# sb5.net
KiCad netlist of a schematic drawn in EAGLE
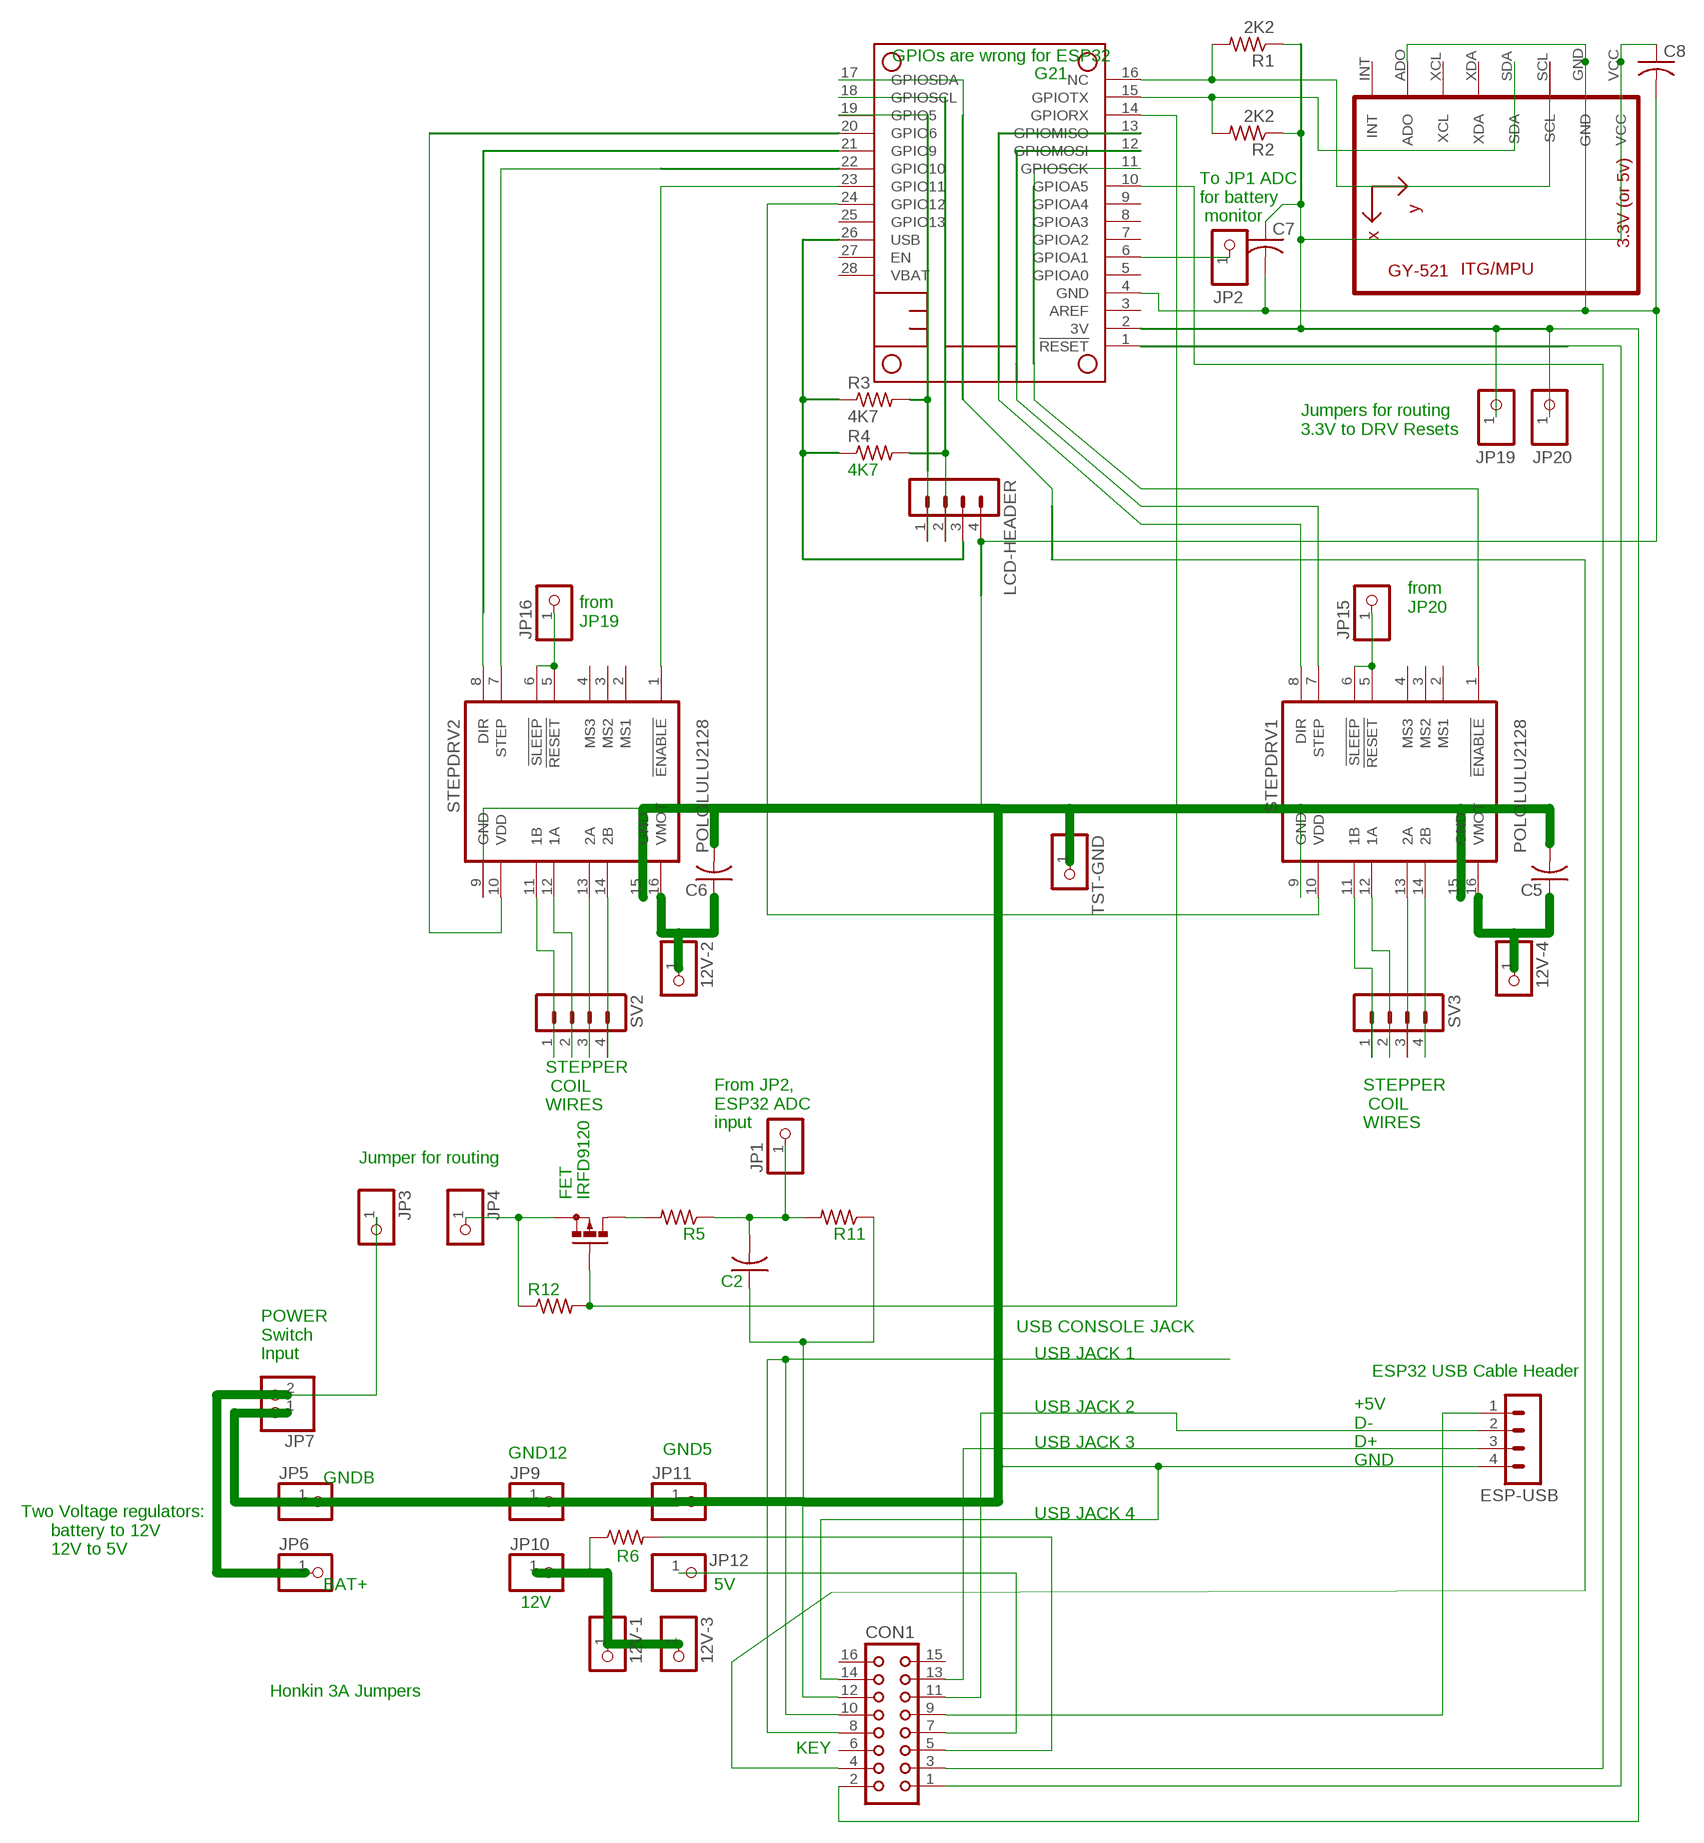
[diagram p0: schematic, sheet 1]

(export (version "E")
  (design (tool "Eeschema 10.0.6"))
  (components
    (comp (ref "12V-1")
      (value "PINHD-1X1")
      (footprint "eagle-import:1X01")
      (libsource (lib "eagle-import") (part "PINHD-1X1"))
    )
    (comp (ref "12V-2")
      (value "PINHD-1X1")
      (footprint "eagle-import:1X01")
      (libsource (lib "eagle-import") (part "PINHD-1X1"))
    )
    (comp (ref "12V-3")
      (value "PINHD-1X1")
      (footprint "eagle-import:1X01")
      (libsource (lib "eagle-import") (part "PINHD-1X1"))
    )
    (comp (ref "12V-4")
      (value "PINHD-1X1")
      (footprint "eagle-import:1X01")
      (libsource (lib "eagle-import") (part "PINHD-1X1"))
    )
    (comp (ref "C2")
      (value "C-US050-025X075")
      (footprint "eagle-import:C050-025X075")
      (libsource (lib "eagle-import") (part "C-US050-025X075"))
    )
    (comp (ref "C5")
      (value "C-US050-024X044")
      (footprint "eagle-import:C050-024X044")
      (libsource (lib "eagle-import") (part "C-US050-024X044"))
    )
    (comp (ref "C6")
      (value "C-US050-024X044")
      (footprint "eagle-import:C050-024X044")
      (libsource (lib "eagle-import") (part "C-US050-024X044"))
    )
    (comp (ref "C7")
      (value "C-US050-024X044")
      (footprint "eagle-import:C050-024X044")
      (libsource (lib "eagle-import") (part "C-US050-024X044"))
    )
    (comp (ref "C8")
      (value "C-US050-024X044")
      (footprint "eagle-import:C050-024X044")
      (libsource (lib "eagle-import") (part "C-US050-024X044"))
    )
    (comp (ref "CON1")
      (value "CON16")
      (footprint "eagle-import:CON16")
      (libsource (lib "eagle-import") (part "CON16"))
    )
    (comp (ref "ESP-USB")
      (value "MA04-1")
      (footprint "eagle-import:MA04-1")
      (libsource (lib "eagle-import") (part "MA04-1"))
    )
    (comp (ref "FET")
      (value "IRFD9120")
      (footprint "eagle-import:C370-01")
      (libsource (lib "eagle-import") (part "IRFD9120"))
    )
    (comp (ref "JP1")
      (value "PINHD-1X1")
      (footprint "eagle-import:1X01")
      (libsource (lib "eagle-import") (part "PINHD-1X1"))
    )
    (comp (ref "JP2")
      (value "PINHD-1X1")
      (footprint "eagle-import:1X01")
      (libsource (lib "eagle-import") (part "PINHD-1X1"))
    )
    (comp (ref "JP3")
      (value "PINHD-1X1")
      (footprint "eagle-import:1X01")
      (libsource (lib "eagle-import") (part "PINHD-1X1"))
    )
    (comp (ref "JP4")
      (value "PINHD-1X1")
      (footprint "eagle-import:1X01")
      (libsource (lib "eagle-import") (part "PINHD-1X1"))
    )
    (comp (ref "JP5")
      (value "PINHD-1X1")
      (footprint "eagle-import:1X01")
      (libsource (lib "eagle-import") (part "PINHD-1X1"))
    )
    (comp (ref "JP6")
      (value "PINHD-1X1")
      (footprint "eagle-import:1X01")
      (libsource (lib "eagle-import") (part "PINHD-1X1"))
    )
    (comp (ref "JP7")
      (value "PINHD-1X2")
      (footprint "eagle-import:1X02")
      (libsource (lib "eagle-import") (part "PINHD-1X2"))
    )
    (comp (ref "JP9")
      (value "PINHD-1X1")
      (footprint "eagle-import:1X01")
      (libsource (lib "eagle-import") (part "PINHD-1X1"))
    )
    (comp (ref "JP10")
      (value "PINHD-1X1")
      (footprint "eagle-import:1X01")
      (libsource (lib "eagle-import") (part "PINHD-1X1"))
    )
    (comp (ref "JP11")
      (value "PINHD-1X1")
      (footprint "eagle-import:1X01")
      (libsource (lib "eagle-import") (part "PINHD-1X1"))
    )
    (comp (ref "JP12")
      (value "PINHD-1X1")
      (footprint "eagle-import:1X01")
      (libsource (lib "eagle-import") (part "PINHD-1X1"))
    )
    (comp (ref "JP15")
      (value "PINHD-1X1")
      (footprint "eagle-import:1X01")
      (libsource (lib "eagle-import") (part "PINHD-1X1"))
    )
    (comp (ref "JP16")
      (value "PINHD-1X1")
      (footprint "eagle-import:1X01")
      (libsource (lib "eagle-import") (part "PINHD-1X1"))
    )
    (comp (ref "JP19")
      (value "PINHD-1X1")
      (footprint "eagle-import:1X01")
      (libsource (lib "eagle-import") (part "PINHD-1X1"))
    )
    (comp (ref "JP20")
      (value "PINHD-1X1")
      (footprint "eagle-import:1X01")
      (libsource (lib "eagle-import") (part "PINHD-1X1"))
    )
    (comp (ref "LCD-HEADER")
      (value "MA04-1")
      (footprint "eagle-import:MA04-1")
      (libsource (lib "eagle-import") (part "MA04-1"))
    )
    (comp (ref "MS2")
      (value "FEATHERWING_NOHOLES")
      (footprint "eagle-import:FEATHERWING_NOHOLES")
      (libsource (lib "eagle-import") (part "FEATHERWING_NOHOLES"))
    )
    (comp (ref "R1")
      (value "2K2")
      (footprint "eagle-import:0309_12")
      (libsource (lib "eagle-import") (part "resistor_348_R-US_0309/12"))
    )
    (comp (ref "R2")
      (value "2K2")
      (footprint "eagle-import:0309_12")
      (libsource (lib "eagle-import") (part "resistor_348_R-US_0309/12"))
    )
    (comp (ref "R3")
      (value "4K7")
      (footprint "eagle-import:0309_12")
      (libsource (lib "eagle-import") (part "resistor_348_R-US_0309/12"))
    )
    (comp (ref "R4")
      (value "4K7")
      (footprint "eagle-import:0309_12")
      (libsource (lib "eagle-import") (part "resistor_348_R-US_0309/12"))
    )
    (comp (ref "R5")
      (value "R-US_0207/10")
      (footprint "eagle-import:0207_10")
      (libsource (lib "eagle-import") (part "R-US_0207/10"))
    )
    (comp (ref "R6")
      (value "R-US_0207/10")
      (footprint "eagle-import:0207_10")
      (libsource (lib "eagle-import") (part "R-US_0207/10"))
    )
    (comp (ref "R11")
      (value "R-US_0207/10")
      (footprint "eagle-import:0207_10")
      (libsource (lib "eagle-import") (part "R-US_0207/10"))
    )
    (comp (ref "R12")
      (value "R-US_0207/10")
      (footprint "eagle-import:0207_10")
      (libsource (lib "eagle-import") (part "R-US_0207/10"))
    )
    (comp (ref "STEPDRV1")
      (value "POLOLULU2128")
      (footprint "eagle-import:POLOLULU2128")
      (libsource (lib "eagle-import") (part "POLOLULU2128"))
    )
    (comp (ref "STEPDRV2")
      (value "POLOLULU2128")
      (footprint "eagle-import:POLOLULU2128")
      (libsource (lib "eagle-import") (part "POLOLULU2128"))
    )
    (comp (ref "SV2")
      (value "MA04-1")
      (footprint "eagle-import:MA04-1")
      (libsource (lib "eagle-import") (part "MA04-1"))
    )
    (comp (ref "SV3")
      (value "MA04-1")
      (footprint "eagle-import:MA04-1")
      (libsource (lib "eagle-import") (part "MA04-1"))
    )
    (comp (ref "TST-GND")
      (value "PINHD-1X1")
      (footprint "eagle-import:1X01")
      (libsource (lib "eagle-import") (part "PINHD-1X1"))
    )
    (comp (ref "U1")
      (value "GY-521MPU6050")
      (footprint "eagle-import:GY-521")
      (libsource (lib "eagle-import") (part "GY-521MPU6050"))
    )
  )
  (nets
    (net (code "1") (name "/VBAT") (class "Default")
      (node (ref "MS2") (pin "28") (pinfunction "VBAT_28") (pintype "power_in"))
    )
    (net (code "2") (name "Net-(12V-1-Pad1)") (class "Default")
      (node (ref "12V-1") (pin "1") (pinfunction "1_1") (pintype "passive"))
      (node (ref "12V-3") (pin "1") (pinfunction "1_1") (pintype "passive"))
      (node (ref "JP10") (pin "1") (pinfunction "1_1") (pintype "passive"))
      (node (ref "R6") (pin "1") (pinfunction "1_1") (pintype "passive"))
    )
    (net (code "3") (name "Net-(C2-Pad2)") (class "Default")
      (node (ref "C2") (pin "2") (pinfunction "2_2") (pintype "passive"))
      (node (ref "JP1") (pin "1") (pinfunction "1_1") (pintype "passive"))
      (node (ref "R11") (pin "2") (pinfunction "2_2") (pintype "passive"))
      (node (ref "R5") (pin "1") (pinfunction "1_1") (pintype "passive"))
    )
    (net (code "4") (name "Net-(CON1-Pad5)") (class "Default")
      (node (ref "CON1") (pin "5") (pinfunction "5_5") (pintype "passive"))
      (node (ref "R6") (pin "2") (pinfunction "2_2") (pintype "passive"))
    )
    (net (code "5") (name "Net-(CON1-Pad7)") (class "Default")
      (node (ref "CON1") (pin "7") (pinfunction "7_7") (pintype "passive"))
      (node (ref "JP12") (pin "1") (pinfunction "1_1") (pintype "passive"))
    )
    (net (code "6") (name "Net-(CON1-Pad9)") (class "Default")
      (node (ref "CON1") (pin "9") (pinfunction "9_9") (pintype "passive"))
      (node (ref "ESP-USB") (pin "1") (pinfunction "1_1") (pintype "passive"))
    )
    (net (code "7") (name "Net-(CON1-Pad10)") (class "Default")
      (node (ref "CON1") (pin "10") (pinfunction "10_10") (pintype "passive"))
      (node (ref "CON1") (pin "8") (pinfunction "8_8") (pintype "passive"))
    )
    (net (code "8") (name "Net-(CON1-Pad11)") (class "Default")
      (node (ref "CON1") (pin "11") (pinfunction "11_11") (pintype "passive"))
      (node (ref "ESP-USB") (pin "2") (pinfunction "2_2") (pintype "passive"))
    )
    (net (code "9") (name "Net-(CON1-Pad13)") (class "Default")
      (node (ref "CON1") (pin "13") (pinfunction "13_13") (pintype "passive"))
      (node (ref "ESP-USB") (pin "3") (pinfunction "3_3") (pintype "passive"))
    )
    (net (code "10") (name "Net-(FET-D-PadD1)") (class "Default")
      (node (ref "FET") (pin "D") (pinfunction "D_D") (pintype "passive"))
      (node (ref "FET") (pin "D1") (pinfunction "D_D1") (pintype "passive"))
      (node (ref "R5") (pin "2") (pinfunction "2_2") (pintype "passive"))
    )
    (net (code "11") (name "Net-(FET-PadS)") (class "Default")
      (node (ref "FET") (pin "S") (pinfunction "S_S") (pintype "passive"))
      (node (ref "JP4") (pin "1") (pinfunction "1_1") (pintype "passive"))
      (node (ref "R12") (pin "1") (pinfunction "1_1") (pintype "passive"))
    )
    (net (code "12") (name "Net-(JP3-Pad1)") (class "Default")
      (node (ref "JP3") (pin "1") (pinfunction "1_1") (pintype "passive"))
      (node (ref "JP6") (pin "1") (pinfunction "1_1") (pintype "passive"))
      (node (ref "JP7") (pin "2") (pinfunction "2_2") (pintype "passive"))
    )
    (net (code "13") (name "Net-(MS2-3V)") (class "Default")
      (node (ref "C7") (pin "1") (pinfunction "1_1") (pintype "passive"))
      (node (ref "C8") (pin "1") (pinfunction "1_1") (pintype "passive"))
      (node (ref "CON1") (pin "2") (pinfunction "2_2") (pintype "passive"))
      (node (ref "JP19") (pin "1") (pinfunction "1_1") (pintype "passive"))
      (node (ref "JP20") (pin "1") (pinfunction "1_1") (pintype "passive"))
      (node (ref "MS2") (pin "2") (pinfunction "3V_2") (pintype "power_in"))
      (node (ref "R1") (pin "1") (pinfunction "1_1") (pintype "passive"))
      (node (ref "R2") (pin "1") (pinfunction "1_1") (pintype "passive"))
      (node (ref "U1") (pin "VCC") (pinfunction "VCC_VCC") (pintype "bidirectional"))
    )
    (net (code "14") (name "Net-(MS2-GND)") (class "Default")
      (node (ref "C2") (pin "1") (pinfunction "1_1") (pintype "passive"))
      (node (ref "C5") (pin "2") (pinfunction "2_2") (pintype "passive"))
      (node (ref "C6") (pin "2") (pinfunction "2_2") (pintype "passive"))
      (node (ref "C7") (pin "2") (pinfunction "2_2") (pintype "passive"))
      (node (ref "C8") (pin "2") (pinfunction "2_2") (pintype "passive"))
      (node (ref "CON1") (pin "12") (pinfunction "12_12") (pintype "passive"))
      (node (ref "CON1") (pin "14") (pinfunction "14_14") (pintype "passive"))
      (node (ref "ESP-USB") (pin "4") (pinfunction "4_4") (pintype "passive"))
      (node (ref "JP11") (pin "1") (pinfunction "1_1") (pintype "passive"))
      (node (ref "JP5") (pin "1") (pinfunction "1_1") (pintype "passive"))
      (node (ref "JP7") (pin "1") (pinfunction "1_1") (pintype "passive"))
      (node (ref "JP9") (pin "1") (pinfunction "1_1") (pintype "passive"))
      (node (ref "LCD-HEADER") (pin "4") (pinfunction "4_4") (pintype "passive"))
      (node (ref "MS2") (pin "4") (pinfunction "GND_4") (pintype "power_in"))
      (node (ref "R11") (pin "1") (pinfunction "1_1") (pintype "passive"))
      (node (ref "STEPDRV1") (pin "15") (pinfunction "GND_15") (pintype "power_in"))
      (node (ref "STEPDRV1") (pin "9") (pinfunction "GND_9") (pintype "power_in"))
      (node (ref "STEPDRV2") (pin "15") (pinfunction "GND_15") (pintype "power_in"))
      (node (ref "STEPDRV2") (pin "9") (pinfunction "GND_9") (pintype "power_in"))
      (node (ref "TST-GND") (pin "1") (pinfunction "1_1") (pintype "passive"))
      (node (ref "U1") (pin "ADO") (pinfunction "ADO_ADO") (pintype "bidirectional"))
      (node (ref "U1") (pin "GND") (pinfunction "GND_GND") (pintype "bidirectional"))
    )
    (net (code "15") (name "Net-(MS2-GPIO5)") (class "Default")
      (node (ref "LCD-HEADER") (pin "1") (pinfunction "1_1") (pintype "passive"))
      (node (ref "MS2") (pin "19") (pinfunction "GPIO5_19") (pintype "bidirectional"))
      (node (ref "R3") (pin "2") (pinfunction "2_2") (pintype "passive"))
    )
    (net (code "16") (name "Net-(MS2-GPIO6)") (class "Default")
      (node (ref "MS2") (pin "20") (pinfunction "GPIO6_20") (pintype "bidirectional"))
      (node (ref "STEPDRV2") (pin "10") (pinfunction "VDD_10") (pintype "power_in"))
    )
    (net (code "17") (name "Net-(MS2-GPIO9)") (class "Default")
      (node (ref "MS2") (pin "21") (pinfunction "GPIO9_21") (pintype "bidirectional"))
      (node (ref "STEPDRV2") (pin "8") (pinfunction "DIR_8") (pintype "input"))
    )
    (net (code "18") (name "Net-(MS2-GPIO10)") (class "Default")
      (node (ref "MS2") (pin "22") (pinfunction "GPIO10_22") (pintype "bidirectional"))
      (node (ref "STEPDRV2") (pin "7") (pinfunction "STEP_7") (pintype "input"))
    )
    (net (code "19") (name "Net-(MS2-GPIO11)") (class "Default")
      (node (ref "MS2") (pin "23") (pinfunction "GPIO11_23") (pintype "bidirectional"))
      (node (ref "STEPDRV2") (pin "1") (pinfunction "~{ENABLE}_1") (pintype "input"))
    )
    (net (code "20") (name "Net-(MS2-GPIO12)") (class "Default")
      (node (ref "MS2") (pin "24") (pinfunction "GPIO12_24") (pintype "bidirectional"))
      (node (ref "STEPDRV1") (pin "10") (pinfunction "VDD_10") (pintype "power_in"))
    )
    (net (code "21") (name "Net-(MS2-GPIOA1)") (class "Default")
      (node (ref "JP2") (pin "1") (pinfunction "1_1") (pintype "passive"))
      (node (ref "MS2") (pin "6") (pinfunction "GPIOA1_6") (pintype "bidirectional"))
    )
    (net (code "22") (name "Net-(MS2-GPIOA5)") (class "Default")
      (node (ref "CON1") (pin "3") (pinfunction "3_3") (pintype "passive"))
      (node (ref "MS2") (pin "10") (pinfunction "GPIOA5_10") (pintype "bidirectional"))
    )
    (net (code "23") (name "Net-(MS2-GPIOMISO)") (class "Default")
      (node (ref "MS2") (pin "13") (pinfunction "GPIOMISO_13") (pintype "bidirectional"))
      (node (ref "STEPDRV1") (pin "8") (pinfunction "DIR_8") (pintype "input"))
    )
    (net (code "24") (name "Net-(MS2-GPIOMOSI)") (class "Default")
      (node (ref "MS2") (pin "12") (pinfunction "GPIOMOSI_12") (pintype "bidirectional"))
      (node (ref "STEPDRV1") (pin "7") (pinfunction "STEP_7") (pintype "input"))
    )
    (net (code "25") (name "Net-(MS2-GPIORX)") (class "Default")
      (node (ref "FET") (pin "G") (pinfunction "G_G") (pintype "passive"))
      (node (ref "MS2") (pin "14") (pinfunction "GPIORX_14") (pintype "bidirectional"))
      (node (ref "R12") (pin "2") (pinfunction "2_2") (pintype "passive"))
    )
    (net (code "26") (name "Net-(MS2-GPIOSCK)") (class "Default")
      (node (ref "MS2") (pin "11") (pinfunction "GPIOSCK_11") (pintype "bidirectional"))
      (node (ref "STEPDRV1") (pin "1") (pinfunction "~{ENABLE}_1") (pintype "input"))
    )
    (net (code "27") (name "Net-(MS2-GPIOSCL)") (class "Default")
      (node (ref "LCD-HEADER") (pin "2") (pinfunction "2_2") (pintype "passive"))
      (node (ref "MS2") (pin "18") (pinfunction "GPIOSCL_18") (pintype "bidirectional"))
      (node (ref "R4") (pin "2") (pinfunction "2_2") (pintype "passive"))
    )
    (net (code "28") (name "Net-(MS2-GPIOSDA)") (class "Default")
      (node (ref "CON1") (pin "4") (pinfunction "4_4") (pintype "passive"))
      (node (ref "MS2") (pin "17") (pinfunction "GPIOSDA_17") (pintype "bidirectional"))
    )
    (net (code "29") (name "Net-(MS2-GPIOTX)") (class "Default")
      (node (ref "MS2") (pin "15") (pinfunction "GPIOTX_15") (pintype "bidirectional"))
      (node (ref "R2") (pin "2") (pinfunction "2_2") (pintype "passive"))
      (node (ref "U1") (pin "SDA") (pinfunction "SDA_SDA") (pintype "bidirectional"))
    )
    (net (code "30") (name "Net-(MS2-NC)") (class "Default")
      (node (ref "MS2") (pin "16") (pinfunction "NC_16") (pintype "passive"))
      (node (ref "R1") (pin "2") (pinfunction "2_2") (pintype "passive"))
      (node (ref "U1") (pin "SCL") (pinfunction "SCL_SCL") (pintype "bidirectional"))
    )
    (net (code "31") (name "Net-(MS2-USB)") (class "Default")
      (node (ref "LCD-HEADER") (pin "3") (pinfunction "3_3") (pintype "passive"))
      (node (ref "MS2") (pin "26") (pinfunction "USB_26") (pintype "power_in"))
      (node (ref "R3") (pin "1") (pinfunction "1_1") (pintype "passive"))
      (node (ref "R4") (pin "1") (pinfunction "1_1") (pintype "passive"))
    )
    (net (code "32") (name "Net-(MS2-~{RESET})") (class "Default")
      (node (ref "CON1") (pin "1") (pinfunction "1_1") (pintype "passive"))
      (node (ref "MS2") (pin "1") (pinfunction "~{RESET}_1") (pintype "input"))
    )
    (net (code "33") (name "Net-(STEPDRV1-1A)") (class "Default")
      (node (ref "STEPDRV1") (pin "12") (pinfunction "1A_12") (pintype "output"))
      (node (ref "SV3") (pin "2") (pinfunction "2_2") (pintype "passive"))
    )
    (net (code "34") (name "Net-(STEPDRV1-1B)") (class "Default")
      (node (ref "STEPDRV1") (pin "11") (pinfunction "1B_11") (pintype "output"))
      (node (ref "SV3") (pin "1") (pinfunction "1_1") (pintype "passive"))
    )
    (net (code "35") (name "Net-(STEPDRV1-2A)") (class "Default")
      (node (ref "STEPDRV1") (pin "13") (pinfunction "2A_13") (pintype "output"))
      (node (ref "SV3") (pin "3") (pinfunction "3_3") (pintype "passive"))
    )
    (net (code "36") (name "Net-(STEPDRV1-2B)") (class "Default")
      (node (ref "STEPDRV1") (pin "14") (pinfunction "2B_14") (pintype "output"))
      (node (ref "SV3") (pin "4") (pinfunction "4_4") (pintype "passive"))
    )
    (net (code "37") (name "Net-(STEPDRV1-VMOT)") (class "Default")
      (node (ref "12V-4") (pin "1") (pinfunction "1_1") (pintype "passive"))
      (node (ref "C5") (pin "1") (pinfunction "1_1") (pintype "passive"))
      (node (ref "STEPDRV1") (pin "16") (pinfunction "VMOT_16") (pintype "power_in"))
    )
    (net (code "38") (name "Net-(STEPDRV1-~{RESET})") (class "Default")
      (node (ref "JP15") (pin "1") (pinfunction "1_1") (pintype "passive"))
      (node (ref "STEPDRV1") (pin "5") (pinfunction "~{RESET}_5") (pintype "input"))
      (node (ref "STEPDRV1") (pin "6") (pinfunction "~{SLEEP}_6") (pintype "input"))
    )
    (net (code "39") (name "Net-(STEPDRV2-1A)") (class "Default")
      (node (ref "STEPDRV2") (pin "12") (pinfunction "1A_12") (pintype "output"))
      (node (ref "SV2") (pin "2") (pinfunction "2_2") (pintype "passive"))
    )
    (net (code "40") (name "Net-(STEPDRV2-1B)") (class "Default")
      (node (ref "STEPDRV2") (pin "11") (pinfunction "1B_11") (pintype "output"))
      (node (ref "SV2") (pin "1") (pinfunction "1_1") (pintype "passive"))
    )
    (net (code "41") (name "Net-(STEPDRV2-2A)") (class "Default")
      (node (ref "STEPDRV2") (pin "13") (pinfunction "2A_13") (pintype "output"))
      (node (ref "SV2") (pin "3") (pinfunction "3_3") (pintype "passive"))
    )
    (net (code "42") (name "Net-(STEPDRV2-2B)") (class "Default")
      (node (ref "STEPDRV2") (pin "14") (pinfunction "2B_14") (pintype "output"))
      (node (ref "SV2") (pin "4") (pinfunction "4_4") (pintype "passive"))
    )
    (net (code "43") (name "Net-(STEPDRV2-VMOT)") (class "Default")
      (node (ref "12V-2") (pin "1") (pinfunction "1_1") (pintype "passive"))
      (node (ref "C6") (pin "1") (pinfunction "1_1") (pintype "passive"))
      (node (ref "STEPDRV2") (pin "16") (pinfunction "VMOT_16") (pintype "power_in"))
    )
    (net (code "44") (name "Net-(STEPDRV2-~{RESET})") (class "Default")
      (node (ref "JP16") (pin "1") (pinfunction "1_1") (pintype "passive"))
      (node (ref "STEPDRV2") (pin "5") (pinfunction "~{RESET}_5") (pintype "input"))
      (node (ref "STEPDRV2") (pin "6") (pinfunction "~{SLEEP}_6") (pintype "input"))
    )
    (net (code "45") (name "unconnected-(CON1-Pad6)") (class "Default")
      (node (ref "CON1") (pin "6") (pinfunction "6_6") (pintype "passive"))
    )
    (net (code "46") (name "unconnected-(CON1-Pad15)") (class "Default")
      (node (ref "CON1") (pin "15") (pinfunction "15_15") (pintype "passive"))
    )
    (net (code "47") (name "unconnected-(CON1-Pad16)") (class "Default")
      (node (ref "CON1") (pin "16") (pinfunction "16_16") (pintype "passive"))
    )
    (net (code "48") (name "unconnected-(MS2-AREF-Pad3)") (class "Default")
      (node (ref "MS2") (pin "3") (pinfunction "AREF_3") (pintype "passive"))
    )
    (net (code "49") (name "unconnected-(MS2-EN-Pad27)") (class "Default")
      (node (ref "MS2") (pin "27") (pinfunction "EN_27") (pintype "passive"))
    )
    (net (code "50") (name "unconnected-(MS2-GPIO13-Pad25)") (class "Default")
      (node (ref "MS2") (pin "25") (pinfunction "GPIO13_25") (pintype "bidirectional"))
    )
    (net (code "51") (name "unconnected-(MS2-GPIOA0-Pad5)") (class "Default")
      (node (ref "MS2") (pin "5") (pinfunction "GPIOA0_5") (pintype "bidirectional"))
    )
    (net (code "52") (name "unconnected-(MS2-GPIOA2-Pad7)") (class "Default")
      (node (ref "MS2") (pin "7") (pinfunction "GPIOA2_7") (pintype "bidirectional"))
    )
    (net (code "53") (name "unconnected-(MS2-GPIOA3-Pad8)") (class "Default")
      (node (ref "MS2") (pin "8") (pinfunction "GPIOA3_8") (pintype "bidirectional"))
    )
    (net (code "54") (name "unconnected-(MS2-GPIOA4-Pad9)") (class "Default")
      (node (ref "MS2") (pin "9") (pinfunction "GPIOA4_9") (pintype "bidirectional"))
    )
    (net (code "55") (name "unconnected-(STEPDRV1-MS1-Pad2)") (class "Default")
      (node (ref "STEPDRV1") (pin "2") (pinfunction "MS1_2") (pintype "input"))
    )
    (net (code "56") (name "unconnected-(STEPDRV1-MS2-Pad3)") (class "Default")
      (node (ref "STEPDRV1") (pin "3") (pinfunction "MS2_3") (pintype "input"))
    )
    (net (code "57") (name "unconnected-(STEPDRV1-MS3-Pad4)") (class "Default")
      (node (ref "STEPDRV1") (pin "4") (pinfunction "MS3_4") (pintype "input"))
    )
    (net (code "58") (name "unconnected-(STEPDRV2-MS1-Pad2)") (class "Default")
      (node (ref "STEPDRV2") (pin "2") (pinfunction "MS1_2") (pintype "input"))
    )
    (net (code "59") (name "unconnected-(STEPDRV2-MS2-Pad3)") (class "Default")
      (node (ref "STEPDRV2") (pin "3") (pinfunction "MS2_3") (pintype "input"))
    )
    (net (code "60") (name "unconnected-(STEPDRV2-MS3-Pad4)") (class "Default")
      (node (ref "STEPDRV2") (pin "4") (pinfunction "MS3_4") (pintype "input"))
    )
    (net (code "61") (name "unconnected-(U1-PadINT)") (class "Default")
      (node (ref "U1") (pin "INT") (pinfunction "INT_INT") (pintype "bidirectional"))
    )
    (net (code "62") (name "unconnected-(U1-PadXCL)") (class "Default")
      (node (ref "U1") (pin "XCL") (pinfunction "XCL_XCL") (pintype "bidirectional"))
    )
    (net (code "63") (name "unconnected-(U1-PadXDA)") (class "Default")
      (node (ref "U1") (pin "XDA") (pinfunction "XDA_XDA") (pintype "bidirectional"))
    )
  )
)
